# u10-minimal.net
KiCad netlist of a schematic drawn in EAGLE
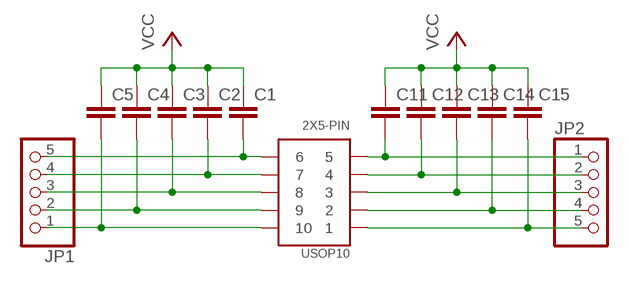
[diagram p0: schematic, sheet 1]

(export (version "E")
  (design (tool "Eeschema 10.0.6"))
  (components
    (comp (ref "C1")
      (value "C-EUC0603")
      (footprint "eagle-import:C0603")
      (libsource (lib "eagle-import") (part "C-EUC0603"))
    )
    (comp (ref "C2")
      (value "C-EUC0603")
      (footprint "eagle-import:C0603")
      (libsource (lib "eagle-import") (part "C-EUC0603"))
    )
    (comp (ref "C3")
      (value "C-EUC0603")
      (footprint "eagle-import:C0603")
      (libsource (lib "eagle-import") (part "C-EUC0603"))
    )
    (comp (ref "C4")
      (value "C-EUC0603")
      (footprint "eagle-import:C0603")
      (libsource (lib "eagle-import") (part "C-EUC0603"))
    )
    (comp (ref "C5")
      (value "C-EUC0603")
      (footprint "eagle-import:C0603")
      (libsource (lib "eagle-import") (part "C-EUC0603"))
    )
    (comp (ref "C11")
      (value "C-EUC0603")
      (footprint "eagle-import:C0603")
      (libsource (lib "eagle-import") (part "C-EUC0603"))
    )
    (comp (ref "C12")
      (value "C-EUC0603")
      (footprint "eagle-import:C0603")
      (libsource (lib "eagle-import") (part "C-EUC0603"))
    )
    (comp (ref "C13")
      (value "C-EUC0603")
      (footprint "eagle-import:C0603")
      (libsource (lib "eagle-import") (part "C-EUC0603"))
    )
    (comp (ref "C14")
      (value "C-EUC0603")
      (footprint "eagle-import:C0603")
      (libsource (lib "eagle-import") (part "C-EUC0603"))
    )
    (comp (ref "C15")
      (value "C-EUC0603")
      (footprint "eagle-import:C0603")
      (libsource (lib "eagle-import") (part "C-EUC0603"))
    )
    (comp (ref "JP1")
      (value "PINHD-1X5")
      (footprint "eagle-import:1X05")
      (libsource (lib "eagle-import") (part "PINHD-1X5"))
    )
    (comp (ref "JP2")
      (value "PINHD-1X5")
      (footprint "eagle-import:1X05")
      (libsource (lib "eagle-import") (part "PINHD-1X5"))
    )
    (comp (ref "USOP10")
      (value "2X5-PIN")
      (footprint "eagle-import:USOP10")
      (libsource (lib "eagle-import") (part "2X5-PIN"))
    )
  )
  (nets
    (net (code "1") (name "Net-(USOP10-1)") (class "Default")
      (node (ref "C15") (pin "2") (pinfunction "2_2") (pintype "passive"))
      (node (ref "JP2") (pin "5") (pinfunction "5_5") (pintype "passive"))
      (node (ref "USOP10") (pin "P$1") (pinfunction "1_P$1") (pintype "bidirectional"))
    )
    (net (code "2") (name "Net-(USOP10-2)") (class "Default")
      (node (ref "C14") (pin "2") (pinfunction "2_2") (pintype "passive"))
      (node (ref "JP2") (pin "4") (pinfunction "4_4") (pintype "passive"))
      (node (ref "USOP10") (pin "P$2") (pinfunction "2_P$2") (pintype "bidirectional"))
    )
    (net (code "3") (name "Net-(USOP10-3)") (class "Default")
      (node (ref "C13") (pin "2") (pinfunction "2_2") (pintype "passive"))
      (node (ref "JP2") (pin "3") (pinfunction "3_3") (pintype "passive"))
      (node (ref "USOP10") (pin "P$3") (pinfunction "3_P$3") (pintype "bidirectional"))
    )
    (net (code "4") (name "Net-(USOP10-4)") (class "Default")
      (node (ref "C12") (pin "2") (pinfunction "2_2") (pintype "passive"))
      (node (ref "JP2") (pin "2") (pinfunction "2_2") (pintype "passive"))
      (node (ref "USOP10") (pin "P$4") (pinfunction "4_P$4") (pintype "bidirectional"))
    )
    (net (code "5") (name "Net-(USOP10-5)") (class "Default")
      (node (ref "C11") (pin "2") (pinfunction "2_2") (pintype "passive"))
      (node (ref "JP2") (pin "1") (pinfunction "1_1") (pintype "passive"))
      (node (ref "USOP10") (pin "P$5") (pinfunction "5_P$5") (pintype "bidirectional"))
    )
    (net (code "6") (name "Net-(USOP10-6)") (class "Default")
      (node (ref "C1") (pin "2") (pinfunction "2_2") (pintype "passive"))
      (node (ref "JP1") (pin "5") (pinfunction "5_5") (pintype "passive"))
      (node (ref "USOP10") (pin "P$6") (pinfunction "6_P$6") (pintype "bidirectional"))
    )
    (net (code "7") (name "Net-(USOP10-7)") (class "Default")
      (node (ref "C2") (pin "2") (pinfunction "2_2") (pintype "passive"))
      (node (ref "JP1") (pin "4") (pinfunction "4_4") (pintype "passive"))
      (node (ref "USOP10") (pin "P$7") (pinfunction "7_P$7") (pintype "bidirectional"))
    )
    (net (code "8") (name "Net-(USOP10-8)") (class "Default")
      (node (ref "C3") (pin "2") (pinfunction "2_2") (pintype "passive"))
      (node (ref "JP1") (pin "3") (pinfunction "3_3") (pintype "passive"))
      (node (ref "USOP10") (pin "P$8") (pinfunction "8_P$8") (pintype "bidirectional"))
    )
    (net (code "9") (name "Net-(USOP10-9)") (class "Default")
      (node (ref "C4") (pin "2") (pinfunction "2_2") (pintype "passive"))
      (node (ref "JP1") (pin "2") (pinfunction "2_2") (pintype "passive"))
      (node (ref "USOP10") (pin "P$9") (pinfunction "9_P$9") (pintype "bidirectional"))
    )
    (net (code "10") (name "Net-(USOP10-10)") (class "Default")
      (node (ref "C5") (pin "2") (pinfunction "2_2") (pintype "passive"))
      (node (ref "JP1") (pin "1") (pinfunction "1_1") (pintype "passive"))
      (node (ref "USOP10") (pin "P$10") (pinfunction "10_P$10") (pintype "bidirectional"))
    )
    (net (code "11") (name "VCC") (class "Default")
      (node (ref "C1") (pin "1") (pinfunction "1_1") (pintype "passive"))
      (node (ref "C11") (pin "1") (pinfunction "1_1") (pintype "passive"))
      (node (ref "C12") (pin "1") (pinfunction "1_1") (pintype "passive"))
      (node (ref "C13") (pin "1") (pinfunction "1_1") (pintype "passive"))
      (node (ref "C14") (pin "1") (pinfunction "1_1") (pintype "passive"))
      (node (ref "C15") (pin "1") (pinfunction "1_1") (pintype "passive"))
      (node (ref "C2") (pin "1") (pinfunction "1_1") (pintype "passive"))
      (node (ref "C3") (pin "1") (pinfunction "1_1") (pintype "passive"))
      (node (ref "C4") (pin "1") (pinfunction "1_1") (pintype "passive"))
      (node (ref "C5") (pin "1") (pinfunction "1_1") (pintype "passive"))
    )
  )
)
